# Buzzer.net
KiCad netlist of a schematic drawn in Altium Designer
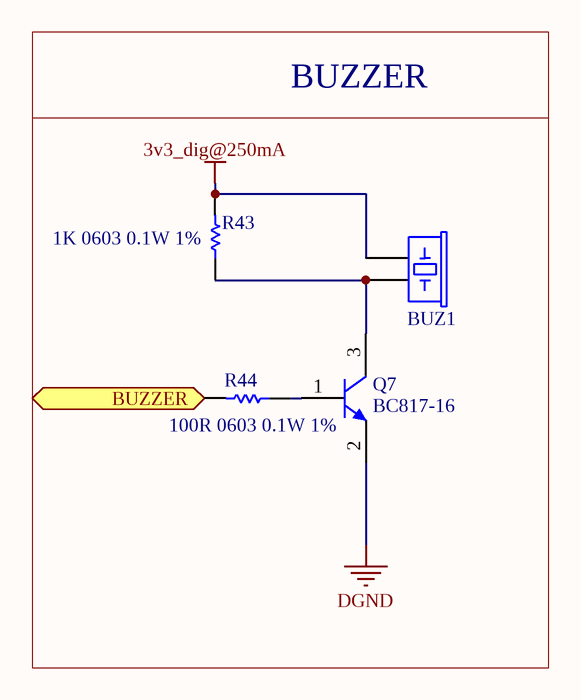
[diagram p0: Buzzer.SchDoc]

(export (version "E")
  (design (tool "Eeschema 10.0.6"))
  (components
    (comp (ref "BUZ1")
      (value "CUI CMT-1285C-035")
      (footprint "BUZZER-12MM-NS")
      (description "Audio Buzzer Magnetic 3Vo-p 5Vo-p 70mA 3.5Vo-p 85dB Through Hole Pin Tray")
      (fields (field (name "MANUFACTURER PART NUMBER") "CMT-1285C-035"))
      (libsource (lib "CommunityVault") (part "CMP-581a9557be5887dd-1"))
    )
    (comp (ref "Q7")
      (value "BC817-16")
      (footprint "PCB-856332-1")
      (description "TRANS NPN 45V 500mA SMD SOT23-3")
      (libsource (lib "CommunityVault") (part "CMP-856332-3"))
    )
    (comp (ref "R43")
      (value "1K 0603 0.1W 1%")
      (footprint "RESC1609X55X30ML10T20")
      (fields (field (name "MANUFACTURER PART NUMBER") "CR0603-FX-1001ELF"))
      (libsource (lib "CommunityVault") (part "CMP-a61f6f36030f79d8-4"))
    )
    (comp (ref "R44")
      (value "100R 0603 0.1W 1%")
      (footprint "RESC1609X55X30ML10T20")
      (fields (field (name "MANUFACTURER PART NUMBER") "ERJ3GEYJ101V"))
      (libsource (lib "CommunityVault") (part "CMP-a61f6f36030f79d8-4"))
    )
  )
  (nets
    (net (code "1") (name "/BUZZER") (class "Default")
      (node (ref "R44") (pin "2") (pinfunction "2_2") (pintype "passive"))
    )
    (net (code "2") (name "3v3_dig@250mA") (class "Default")
      (node (ref "BUZ1") (pin "1") (pinfunction "+_1") (pintype "passive"))
      (node (ref "R43") (pin "2") (pinfunction "2_2") (pintype "passive"))
    )
    (net (code "3") (name "DGND") (class "Default")
      (node (ref "Q7") (pin "2") (pinfunction "E_2") (pintype "passive"))
    )
    (net (code "4") (name "Net-(BUZ1--)") (class "Default")
      (node (ref "BUZ1") (pin "2") (pinfunction "-_2") (pintype "passive"))
      (node (ref "Q7") (pin "3") (pinfunction "C_3") (pintype "passive"))
      (node (ref "R43") (pin "1") (pinfunction "1_1") (pintype "passive"))
    )
    (net (code "5") (name "Net-(Q7-B)") (class "Default")
      (node (ref "Q7") (pin "1") (pinfunction "B_1") (pintype "passive"))
      (node (ref "R44") (pin "1") (pinfunction "1_1") (pintype "passive"))
    )
  )
)
